# ESP.net
KiCad netlist of a schematic drawn in Altium Designer
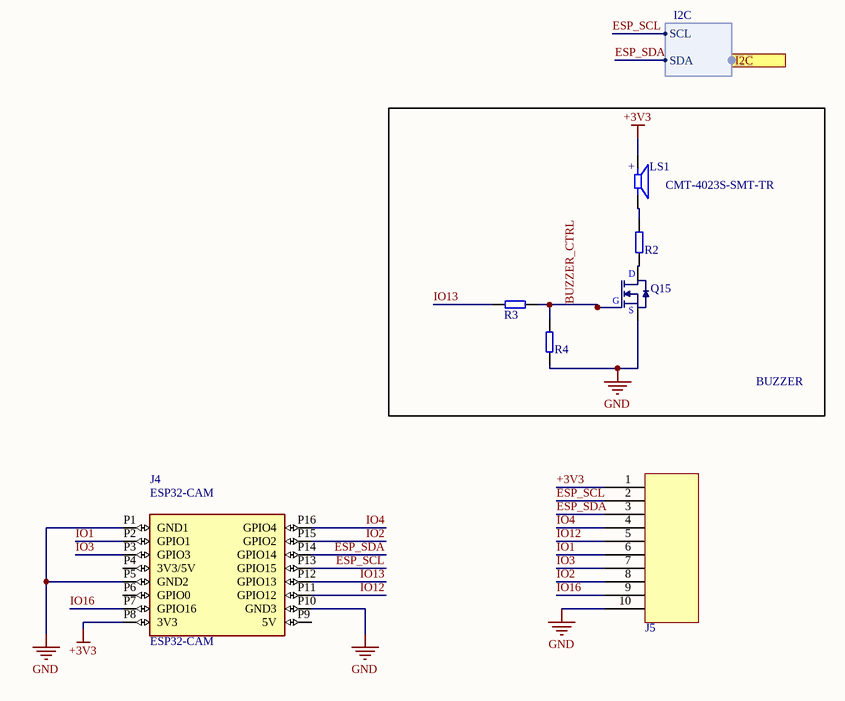
[diagram p0: ESP.SchDoc]

(export (version "E")
  (design (tool "Eeschema 10.0.6"))
  (components
    (comp (ref "J4")
      (value "ESP32-CAM")
      (footprint "ESP32-CAM")
      (description "CAMERA MODULE")
      (fields (field (name "MF") "AI-Thinker"))
      (libsource (lib "anayurt") (part "ESP32-CAM"))
    )
    (comp (ref "J5")
      (value "54202-T0805LF")
      (footprint "10P_2.54MM_SMD")
      (description "CONN HEADER SMD 10POS 2.54MM")
      (fields (field (name "MANUFACTURER") "Amphenol ICC (FCI)"))
      (libsource (lib "anayurt") (part "CONN10P_1R"))
    )
    (comp (ref "LS1")
      (value "CMT-4023S-SMT-TR")
      (footprint "Buzzer")
      (description "AUDIO MAGNETIC XDCR 2-4V SMD")
      (fields
        (field (name "MANUFACTURER") "CUI")
        (field (name "MANUFACTURER PART NUMBER") "CMT-4023S-SMT-TR")
      )
      (libsource (lib "coconut_MB") (part "CMT-4023S-SMT-TR"))
    )
    (comp (ref "Q15")
      (value "NTK3043NT1G")
      (footprint "SOT-723")
      (description "MOSFET N-CH 20V 210MA SOT723")
      (fields (field (name "VOLTAGE") "1.65V, 4.5V") (field (name "MANUFACTURER") "ON Semiconductor"))
      (libsource (lib "anayurt") (part "NMOS"))
    )
    (comp (ref "R2")
      (value "1K")
      (footprint "R0402")
      (description "RES SMD 1K OHM 0.1% 1/16W 0402")
      (fields (field (name "PART NUMBER") "RT0402BRE071KL") (field (name "TOLERANCE") "0.1%"))
      (libsource (lib "anayurt") (part "RES"))
    )
    (comp (ref "R3")
      (value "1K")
      (footprint "R0402")
      (description "RES SMD 1K OHM 0.1% 1/16W 0402")
      (fields (field (name "PART NUMBER") "RT0402BRE071KL") (field (name "TOLERANCE") "0.1%"))
      (libsource (lib "anayurt") (part "RES"))
    )
    (comp (ref "R4")
      (value "1K")
      (footprint "R0402")
      (description "RES SMD 1K OHM 0.1% 1/16W 0402")
      (fields (field (name "PART NUMBER") "RT0402BRE071KL") (field (name "TOLERANCE") "0.1%"))
      (libsource (lib "anayurt") (part "RES"))
    )
  )
  (nets
    (net (code "2") (name "+3V3") (class "Default")
      (node (ref "J4") (pin "P8") (pinfunction "3V3_P8") (pintype "bidirectional"))
      (node (ref "J5") (pin "1") (pinfunction "1_1") (pintype "passive"))
      (node (ref "LS1") (pin "P") (pinfunction "P_P") (pintype "passive"))
    )
    (net (code "3") (name "/BUZZER_CTRL") (class "Default")
      (node (ref "Q15") (pin "1") (pinfunction "G_1") (pintype "passive"))
      (node (ref "R3") (pin "2") (pinfunction "2_2") (pintype "passive"))
      (node (ref "R4") (pin "2") (pinfunction "2_2") (pintype "passive"))
    )
    (net (code "4") (name "/ESP_SCL") (class "Default")
      (node (ref "J4") (pin "P13") (pinfunction "GPIO15_P13") (pintype "bidirectional"))
      (node (ref "J5") (pin "2") (pinfunction "2_2") (pintype "passive"))
    )
    (net (code "5") (name "/ESP_SDA") (class "Default")
      (node (ref "J4") (pin "P14") (pinfunction "GPIO14_P14") (pintype "bidirectional"))
      (node (ref "J5") (pin "3") (pinfunction "3_3") (pintype "passive"))
    )
    (net (code "6") (name "/IO1") (class "Default")
      (node (ref "J4") (pin "P2") (pinfunction "GPIO1_P2") (pintype "bidirectional"))
      (node (ref "J5") (pin "6") (pinfunction "6_6") (pintype "passive"))
    )
    (net (code "7") (name "/IO2") (class "Default")
      (node (ref "J4") (pin "P15") (pinfunction "GPIO2_P15") (pintype "bidirectional"))
      (node (ref "J5") (pin "8") (pinfunction "8_8") (pintype "passive"))
    )
    (net (code "8") (name "/IO3") (class "Default")
      (node (ref "J4") (pin "P3") (pinfunction "GPIO3_P3") (pintype "bidirectional"))
      (node (ref "J5") (pin "7") (pinfunction "7_7") (pintype "passive"))
    )
    (net (code "9") (name "/IO4") (class "Default")
      (node (ref "J4") (pin "P16") (pinfunction "GPIO4_P16") (pintype "bidirectional"))
      (node (ref "J5") (pin "4") (pinfunction "4_4") (pintype "passive"))
    )
    (net (code "10") (name "/IO12") (class "Default")
      (node (ref "J4") (pin "P11") (pinfunction "GPIO12_P11") (pintype "bidirectional"))
      (node (ref "J5") (pin "5") (pinfunction "5_5") (pintype "passive"))
    )
    (net (code "11") (name "/IO13") (class "Default")
      (node (ref "J4") (pin "P12") (pinfunction "GPIO13_P12") (pintype "bidirectional"))
      (node (ref "R3") (pin "1") (pinfunction "1_1") (pintype "passive"))
    )
    (net (code "12") (name "/IO16") (class "Default")
      (node (ref "J4") (pin "P7") (pinfunction "GPIO16_P7") (pintype "bidirectional"))
      (node (ref "J5") (pin "9") (pinfunction "9_9") (pintype "passive"))
    )
    (net (code "14") (name "GND") (class "Default")
      (node (ref "J4") (pin "P1") (pinfunction "GND1_P1") (pintype "bidirectional"))
      (node (ref "J4") (pin "P10") (pinfunction "GND3_P10") (pintype "bidirectional"))
      (node (ref "J4") (pin "P5") (pinfunction "GND2_P5") (pintype "bidirectional"))
      (node (ref "J5") (pin "10") (pinfunction "10_10") (pintype "passive"))
      (node (ref "Q15") (pin "2") (pinfunction "S_2") (pintype "passive"))
      (node (ref "R4") (pin "1") (pinfunction "1_1") (pintype "passive"))
    )
    (net (code "15") (name "Net-(LS1-PadN)") (class "Default")
      (node (ref "LS1") (pin "N") (pinfunction "N_N") (pintype "passive"))
      (node (ref "R2") (pin "2") (pinfunction "2_2") (pintype "passive"))
    )
    (net (code "16") (name "Net-(Q15-D)") (class "Default")
      (node (ref "Q15") (pin "3") (pinfunction "D_3") (pintype "passive"))
      (node (ref "R2") (pin "1") (pinfunction "1_1") (pintype "passive"))
    )
    (net (code "17") (name "unconnected-(J4-3V3{slash}5V-PadP4)") (class "Default")
      (node (ref "J4") (pin "P4") (pinfunction "3V3/5V_P4") (pintype "bidirectional"))
    )
    (net (code "18") (name "unconnected-(J4-5V-PadP9)") (class "Default")
      (node (ref "J4") (pin "P9") (pinfunction "5V_P9") (pintype "bidirectional"))
    )
    (net (code "19") (name "unconnected-(J4-GPIO0-PadP6)") (class "Default")
      (node (ref "J4") (pin "P6") (pinfunction "GPIO0_P6") (pintype "bidirectional"))
    )
  )
)
